# ATC1.net
KiCad netlist of a schematic drawn in EAGLE
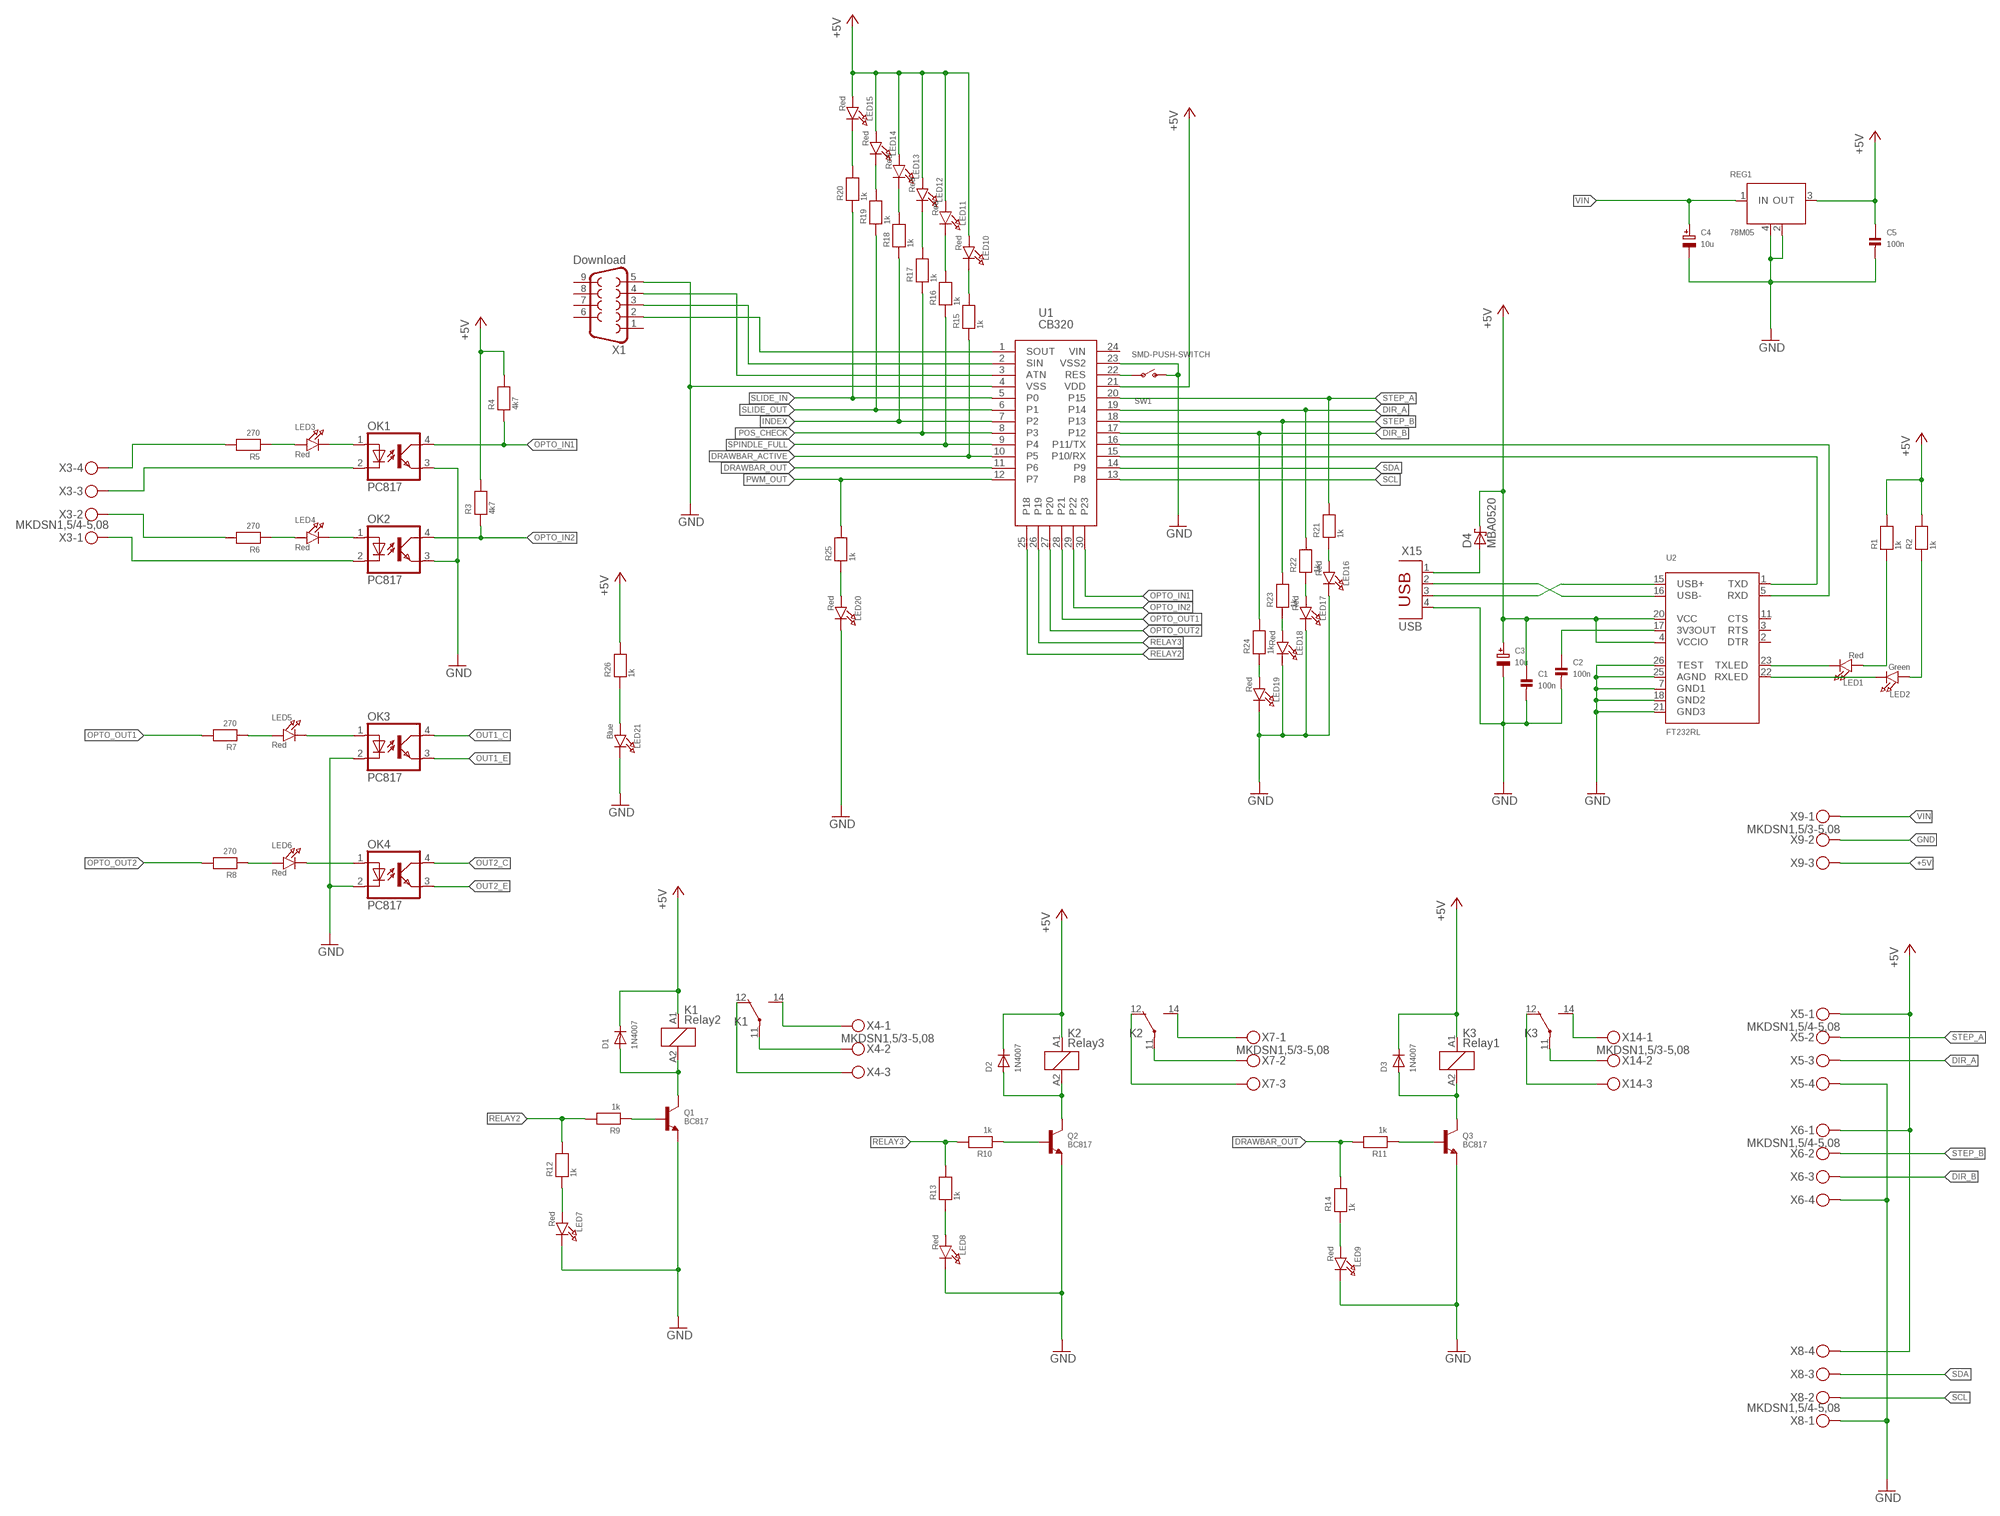
[diagram p0: schematic, sheet 1, part 1 of 2]
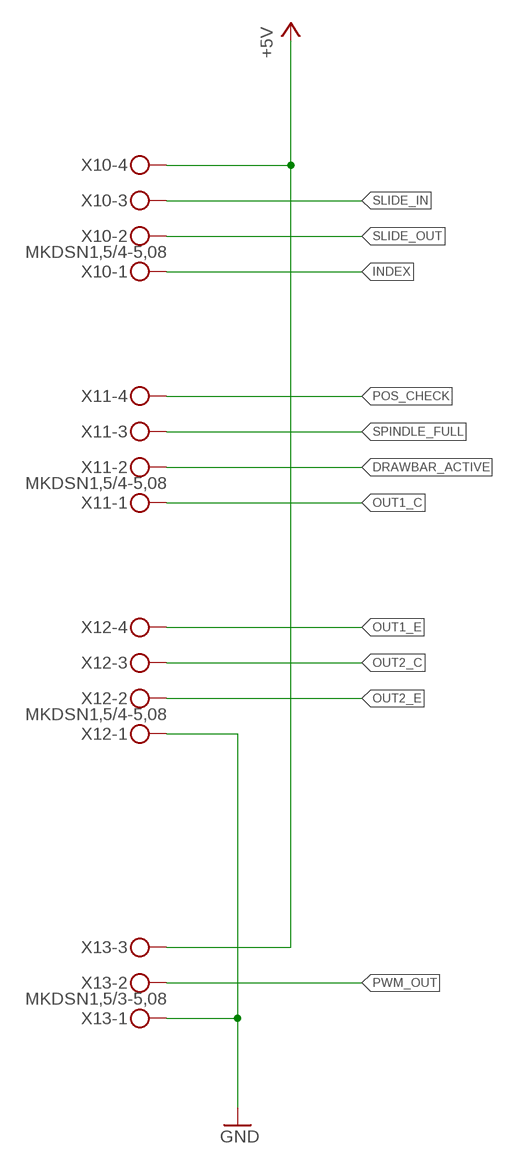
[diagram p1: schematic, sheet 1, part 2 of 2]

(export (version "E")
  (design (tool "Eeschema 10.0.6"))
  (components
    (comp (ref "C1")
      (value "100n")
      (footprint "eagle-import:0805")
      (libsource (lib "eagle-import") (part "CAP_CERAMIC0805"))
    )
    (comp (ref "C2")
      (value "100n")
      (footprint "eagle-import:0805")
      (libsource (lib "eagle-import") (part "CAP_CERAMIC0805"))
    )
    (comp (ref "C3")
      (value "10u")
      (footprint "eagle-import:EIA3216-18_A-R")
      (libsource (lib "eagle-import") (part "CAP_TANTALUMA/3216_REFLOW"))
    )
    (comp (ref "C4")
      (value "10u")
      (footprint "eagle-import:EIA3216-18_A-R")
      (libsource (lib "eagle-import") (part "CAP_TANTALUMA/3216_REFLOW"))
    )
    (comp (ref "C5")
      (value "100n")
      (footprint "eagle-import:0805")
      (libsource (lib "eagle-import") (part "CAP_CERAMIC0805"))
    )
    (comp (ref "D1")
      (value "1N4007")
      (footprint "eagle-import:SOD-123")
      (libsource (lib "eagle-import") (part "DIODESOD-123"))
    )
    (comp (ref "D2")
      (value "1N4007")
      (footprint "eagle-import:SOD-123")
      (libsource (lib "eagle-import") (part "DIODESOD-123"))
    )
    (comp (ref "D3")
      (value "1N4007")
      (footprint "eagle-import:SOD-123")
      (libsource (lib "eagle-import") (part "DIODESOD-123"))
    )
    (comp (ref "D4")
      (value "MBA0520")
      (footprint "eagle-import:SOD123")
      (libsource (lib "eagle-import") (part "MBR0520"))
    )
    (comp (ref "K1")
      (value "Relay2")
      (footprint "eagle-import:SRD")
      (libsource (lib "eagle-import") (part "SRD-05VDC-SL-C"))
    )
    (comp (ref "K2")
      (value "Relay3")
      (footprint "eagle-import:SRD")
      (libsource (lib "eagle-import") (part "SRD-05VDC-SL-C"))
    )
    (comp (ref "K3")
      (value "Relay1")
      (footprint "eagle-import:SRD")
      (libsource (lib "eagle-import") (part "SRD-05VDC-SL-C"))
    )
    (comp (ref "LED1")
      (value "Red")
      (footprint "eagle-import:CHIPLED_0805")
      (libsource (lib "eagle-import") (part "LED0805"))
    )
    (comp (ref "LED2")
      (value "Green")
      (footprint "eagle-import:CHIPLED_0805")
      (libsource (lib "eagle-import") (part "LED0805"))
    )
    (comp (ref "LED3")
      (value "Red")
      (footprint "eagle-import:CHIPLED_0805")
      (libsource (lib "eagle-import") (part "LED0805"))
    )
    (comp (ref "LED4")
      (value "Red")
      (footprint "eagle-import:CHIPLED_0805")
      (libsource (lib "eagle-import") (part "LED0805"))
    )
    (comp (ref "LED5")
      (value "Red")
      (footprint "eagle-import:CHIPLED_0805")
      (libsource (lib "eagle-import") (part "LED0805"))
    )
    (comp (ref "LED6")
      (value "Red")
      (footprint "eagle-import:CHIPLED_0805")
      (libsource (lib "eagle-import") (part "LED0805"))
    )
    (comp (ref "LED7")
      (value "Red")
      (footprint "eagle-import:CHIPLED_0805")
      (libsource (lib "eagle-import") (part "LED0805"))
    )
    (comp (ref "LED8")
      (value "Red")
      (footprint "eagle-import:CHIPLED_0805")
      (libsource (lib "eagle-import") (part "LED0805"))
    )
    (comp (ref "LED9")
      (value "Red")
      (footprint "eagle-import:CHIPLED_0805")
      (libsource (lib "eagle-import") (part "LED0805"))
    )
    (comp (ref "LED10")
      (value "Red")
      (footprint "eagle-import:CHIPLED_0805")
      (libsource (lib "eagle-import") (part "LED0805"))
    )
    (comp (ref "LED11")
      (value "Red")
      (footprint "eagle-import:CHIPLED_0805")
      (libsource (lib "eagle-import") (part "LED0805"))
    )
    (comp (ref "LED12")
      (value "Red")
      (footprint "eagle-import:CHIPLED_0805")
      (libsource (lib "eagle-import") (part "LED0805"))
    )
    (comp (ref "LED13")
      (value "Red")
      (footprint "eagle-import:CHIPLED_0805")
      (libsource (lib "eagle-import") (part "LED0805"))
    )
    (comp (ref "LED14")
      (value "Red")
      (footprint "eagle-import:CHIPLED_0805")
      (libsource (lib "eagle-import") (part "LED0805"))
    )
    (comp (ref "LED15")
      (value "Red")
      (footprint "eagle-import:CHIPLED_0805")
      (libsource (lib "eagle-import") (part "LED0805"))
    )
    (comp (ref "LED16")
      (value "Red")
      (footprint "eagle-import:CHIPLED_0805")
      (libsource (lib "eagle-import") (part "LED0805"))
    )
    (comp (ref "LED17")
      (value "Red")
      (footprint "eagle-import:CHIPLED_0805")
      (libsource (lib "eagle-import") (part "LED0805"))
    )
    (comp (ref "LED18")
      (value "Red")
      (footprint "eagle-import:CHIPLED_0805")
      (libsource (lib "eagle-import") (part "LED0805"))
    )
    (comp (ref "LED19")
      (value "Red")
      (footprint "eagle-import:CHIPLED_0805")
      (libsource (lib "eagle-import") (part "LED0805"))
    )
    (comp (ref "LED20")
      (value "Red")
      (footprint "eagle-import:CHIPLED_0805")
      (libsource (lib "eagle-import") (part "LED0805"))
    )
    (comp (ref "LED21")
      (value "Blue")
      (footprint "eagle-import:CHIPLED_0805")
      (libsource (lib "eagle-import") (part "LED0805"))
    )
    (comp (ref "OK1")
      (value "PC817")
      (footprint "eagle-import:SM4-GW")
      (libsource (lib "eagle-import") (part "PC817"))
    )
    (comp (ref "OK2")
      (value "PC817")
      (footprint "eagle-import:SM4-GW")
      (libsource (lib "eagle-import") (part "PC817"))
    )
    (comp (ref "OK3")
      (value "PC817")
      (footprint "eagle-import:SM4-GW")
      (libsource (lib "eagle-import") (part "PC817"))
    )
    (comp (ref "OK4")
      (value "PC817")
      (footprint "eagle-import:SM4-GW")
      (libsource (lib "eagle-import") (part "PC817"))
    )
    (comp (ref "Q1")
      (value "BC817")
      (footprint "eagle-import:SOT23-WIDE")
      (libsource (lib "eagle-import") (part "TRANSISTOR_NPNWIDE"))
    )
    (comp (ref "Q2")
      (value "BC817")
      (footprint "eagle-import:SOT23-WIDE")
      (libsource (lib "eagle-import") (part "TRANSISTOR_NPNWIDE"))
    )
    (comp (ref "Q3")
      (value "BC817")
      (footprint "eagle-import:SOT23-WIDE")
      (libsource (lib "eagle-import") (part "TRANSISTOR_NPNWIDE"))
    )
    (comp (ref "R1")
      (value "1k")
      (footprint "eagle-import:0805")
      (libsource (lib "eagle-import") (part "RESISTOR0805"))
    )
    (comp (ref "R2")
      (value "1k")
      (footprint "eagle-import:0805")
      (libsource (lib "eagle-import") (part "RESISTOR0805"))
    )
    (comp (ref "R3")
      (value "4k7")
      (footprint "eagle-import:0805")
      (libsource (lib "eagle-import") (part "RESISTOR0805"))
    )
    (comp (ref "R4")
      (value "4k7")
      (footprint "eagle-import:0805")
      (libsource (lib "eagle-import") (part "RESISTOR0805"))
    )
    (comp (ref "R5")
      (value "270")
      (footprint "eagle-import:0805")
      (libsource (lib "eagle-import") (part "RESISTOR0805"))
    )
    (comp (ref "R6")
      (value "270")
      (footprint "eagle-import:0805")
      (libsource (lib "eagle-import") (part "RESISTOR0805"))
    )
    (comp (ref "R7")
      (value "270")
      (footprint "eagle-import:0805")
      (libsource (lib "eagle-import") (part "RESISTOR0805"))
    )
    (comp (ref "R8")
      (value "270")
      (footprint "eagle-import:0805")
      (libsource (lib "eagle-import") (part "RESISTOR0805"))
    )
    (comp (ref "R9")
      (value "1k")
      (footprint "eagle-import:0805")
      (libsource (lib "eagle-import") (part "RESISTOR0805"))
    )
    (comp (ref "R10")
      (value "1k")
      (footprint "eagle-import:0805")
      (libsource (lib "eagle-import") (part "RESISTOR0805"))
    )
    (comp (ref "R11")
      (value "1k")
      (footprint "eagle-import:0805")
      (libsource (lib "eagle-import") (part "RESISTOR0805"))
    )
    (comp (ref "R12")
      (value "1k")
      (footprint "eagle-import:0805")
      (libsource (lib "eagle-import") (part "RESISTOR0805"))
    )
    (comp (ref "R13")
      (value "1k")
      (footprint "eagle-import:0805")
      (libsource (lib "eagle-import") (part "RESISTOR0805"))
    )
    (comp (ref "R14")
      (value "1k")
      (footprint "eagle-import:0805")
      (libsource (lib "eagle-import") (part "RESISTOR0805"))
    )
    (comp (ref "R15")
      (value "1k")
      (footprint "eagle-import:0805")
      (libsource (lib "eagle-import") (part "RESISTOR0805"))
    )
    (comp (ref "R16")
      (value "1k")
      (footprint "eagle-import:0805")
      (libsource (lib "eagle-import") (part "RESISTOR0805"))
    )
    (comp (ref "R17")
      (value "1k")
      (footprint "eagle-import:0805")
      (libsource (lib "eagle-import") (part "RESISTOR0805"))
    )
    (comp (ref "R18")
      (value "1k")
      (footprint "eagle-import:0805")
      (libsource (lib "eagle-import") (part "RESISTOR0805"))
    )
    (comp (ref "R19")
      (value "1k")
      (footprint "eagle-import:0805")
      (libsource (lib "eagle-import") (part "RESISTOR0805"))
    )
    (comp (ref "R20")
      (value "1k")
      (footprint "eagle-import:0805")
      (libsource (lib "eagle-import") (part "RESISTOR0805"))
    )
    (comp (ref "R21")
      (value "1k")
      (footprint "eagle-import:0805")
      (libsource (lib "eagle-import") (part "RESISTOR0805"))
    )
    (comp (ref "R22")
      (value "1k")
      (footprint "eagle-import:0805")
      (libsource (lib "eagle-import") (part "RESISTOR0805"))
    )
    (comp (ref "R23")
      (value "1k")
      (footprint "eagle-import:0805")
      (libsource (lib "eagle-import") (part "RESISTOR0805"))
    )
    (comp (ref "R24")
      (value "1k")
      (footprint "eagle-import:0805")
      (libsource (lib "eagle-import") (part "RESISTOR0805"))
    )
    (comp (ref "R25")
      (value "1k")
      (footprint "eagle-import:0805")
      (libsource (lib "eagle-import") (part "RESISTOR0805"))
    )
    (comp (ref "R26")
      (value "1k")
      (footprint "eagle-import:0805")
      (libsource (lib "eagle-import") (part "RESISTOR0805"))
    )
    (comp (ref "REG1")
      (value "78M05")
      (footprint "eagle-import:UA78M05")
      (libsource (lib "eagle-import") (part "UA78M05"))
    )
    (comp (ref "SW1")
      (value "SMD-PUSH-SWITCH")
      (footprint "eagle-import:PUSH-BUTTON-SMD")
      (libsource (lib "eagle-import") (part "SMD-PUSH-SWITCH"))
    )
    (comp (ref "U1")
      (value "CB320")
      (footprint "eagle-import:DIL24")
      (libsource (lib "eagle-import") (part "CUBLOC-CB320"))
    )
    (comp (ref "U2")
      (value "FT232RL")
      (footprint "eagle-import:SSOP28DB")
      (libsource (lib "eagle-import") (part "FT232RLSSOP28"))
    )
    (comp (ref "X1")
      (value "Download")
      (footprint "eagle-import:F09HP")
      (libsource (lib "eagle-import") (part "F09HP"))
    )
    (comp (ref "X3")
      (value "MKDSN1,5/4-5,08")
      (footprint "eagle-import:MKDSN1,5_4-5,08")
      (libsource (lib "eagle-import") (part "MKDSN1,5/4-5,08"))
    )
    (comp (ref "X4")
      (value "MKDSN1,5/3-5,08")
      (footprint "eagle-import:MKDSN1,5_3-5,08")
      (libsource (lib "eagle-import") (part "MKDSN1,5/3-5,08"))
    )
    (comp (ref "X5")
      (value "MKDSN1,5/4-5,08")
      (footprint "eagle-import:MKDSN1,5_4-5,08")
      (libsource (lib "eagle-import") (part "MKDSN1,5/4-5,08"))
    )
    (comp (ref "X6")
      (value "MKDSN1,5/4-5,08")
      (footprint "eagle-import:MKDSN1,5_4-5,08")
      (libsource (lib "eagle-import") (part "MKDSN1,5/4-5,08"))
    )
    (comp (ref "X7")
      (value "MKDSN1,5/3-5,08")
      (footprint "eagle-import:MKDSN1,5_3-5,08")
      (libsource (lib "eagle-import") (part "MKDSN1,5/3-5,08"))
    )
    (comp (ref "X8")
      (value "MKDSN1,5/4-5,08")
      (footprint "eagle-import:MKDSN1,5_4-5,08")
      (libsource (lib "eagle-import") (part "MKDSN1,5/4-5,08"))
    )
    (comp (ref "X9")
      (value "MKDSN1,5/3-5,08")
      (footprint "eagle-import:MKDSN1,5_3-5,08")
      (libsource (lib "eagle-import") (part "MKDSN1,5/3-5,08"))
    )
    (comp (ref "X10")
      (value "MKDSN1,5/4-5,08")
      (footprint "eagle-import:MKDSN1,5_4-5,08")
      (libsource (lib "eagle-import") (part "MKDSN1,5/4-5,08"))
    )
    (comp (ref "X11")
      (value "MKDSN1,5/4-5,08")
      (footprint "eagle-import:MKDSN1,5_4-5,08")
      (libsource (lib "eagle-import") (part "MKDSN1,5/4-5,08"))
    )
    (comp (ref "X12")
      (value "MKDSN1,5/4-5,08")
      (footprint "eagle-import:MKDSN1,5_4-5,08")
      (libsource (lib "eagle-import") (part "MKDSN1,5/4-5,08"))
    )
    (comp (ref "X13")
      (value "MKDSN1,5/3-5,08")
      (footprint "eagle-import:MKDSN1,5_3-5,08")
      (libsource (lib "eagle-import") (part "MKDSN1,5/3-5,08"))
    )
    (comp (ref "X14")
      (value "MKDSN1,5/3-5,08")
      (footprint "eagle-import:MKDSN1,5_3-5,08")
      (libsource (lib "eagle-import") (part "MKDSN1,5/3-5,08"))
    )
    (comp (ref "X15")
      (value "USB")
      (footprint "eagle-import:PN61729")
      (libsource (lib "eagle-import") (part "PN61729"))
    )
  )
  (nets
    (net (code "1") (name "+5V") (class "Default")
      (node (ref "C1") (pin "1") (pinfunction "P$1_1") (pintype "passive"))
      (node (ref "C3") (pin "+") (pinfunction "+_+") (pintype "passive"))
      (node (ref "C5") (pin "1") (pinfunction "P$1_1") (pintype "passive"))
      (node (ref "D1") (pin "C") (pinfunction "C_C") (pintype "passive"))
      (node (ref "D2") (pin "C") (pinfunction "C_C") (pintype "passive"))
      (node (ref "D3") (pin "C") (pinfunction "C_C") (pintype "passive"))
      (node (ref "D4") (pin "C") (pinfunction "C_C") (pintype "passive"))
      (node (ref "K1") (pin "A1") (pinfunction "1_A1") (pintype "passive"))
      (node (ref "K2") (pin "A1") (pinfunction "1_A1") (pintype "passive"))
      (node (ref "K3") (pin "A1") (pinfunction "1_A1") (pintype "passive"))
      (node (ref "LED10") (pin "A") (pinfunction "A_A") (pintype "passive"))
      (node (ref "LED11") (pin "A") (pinfunction "A_A") (pintype "passive"))
      (node (ref "LED12") (pin "A") (pinfunction "A_A") (pintype "passive"))
      (node (ref "LED13") (pin "A") (pinfunction "A_A") (pintype "passive"))
      (node (ref "LED14") (pin "A") (pinfunction "A_A") (pintype "passive"))
      (node (ref "LED15") (pin "A") (pinfunction "A_A") (pintype "passive"))
      (node (ref "R1") (pin "2") (pinfunction "2_2") (pintype "passive"))
      (node (ref "R2") (pin "2") (pinfunction "2_2") (pintype "passive"))
      (node (ref "R26") (pin "2") (pinfunction "2_2") (pintype "passive"))
      (node (ref "R3") (pin "2") (pinfunction "2_2") (pintype "passive"))
      (node (ref "R4") (pin "2") (pinfunction "2_2") (pintype "passive"))
      (node (ref "REG1") (pin "3") (pinfunction "OUT_3") (pintype "passive"))
      (node (ref "U1") (pin "21") (pinfunction "VDD_21") (pintype "power_in"))
      (node (ref "U2") (pin "20") (pinfunction "VCC_20") (pintype "power_in"))
      (node (ref "U2") (pin "4") (pinfunction "VCCIO_4") (pintype "power_in"))
      (node (ref "X10") (pin "4") (pinfunction "KL_4") (pintype "passive"))
      (node (ref "X13") (pin "3") (pinfunction "KL_3") (pintype "passive"))
      (node (ref "X5") (pin "1") (pinfunction "KL_1") (pintype "passive"))
      (node (ref "X6") (pin "1") (pinfunction "KL_1") (pintype "passive"))
      (node (ref "X8") (pin "4") (pinfunction "KL_4") (pintype "passive"))
      (node (ref "X9") (pin "3") (pinfunction "KL_3") (pintype "passive"))
    )
    (net (code "2") (name "DIR_A") (class "Default")
      (node (ref "R22") (pin "2") (pinfunction "2_2") (pintype "passive"))
      (node (ref "U1") (pin "19") (pinfunction "P14_19") (pintype "bidirectional"))
      (node (ref "X5") (pin "3") (pinfunction "KL_3") (pintype "passive"))
    )
    (net (code "3") (name "DIR_B") (class "Default")
      (node (ref "R24") (pin "2") (pinfunction "2_2") (pintype "passive"))
      (node (ref "U1") (pin "17") (pinfunction "P12_17") (pintype "bidirectional"))
      (node (ref "X6") (pin "3") (pinfunction "KL_3") (pintype "passive"))
    )
    (net (code "4") (name "DRAWBAR_ACTIVE") (class "Default")
      (node (ref "R15") (pin "1") (pinfunction "1_1") (pintype "passive"))
      (node (ref "U1") (pin "10") (pinfunction "P5_10") (pintype "bidirectional"))
      (node (ref "X11") (pin "2") (pinfunction "KL_2") (pintype "passive"))
    )
    (net (code "5") (name "DRAWBAR_OUT") (class "Default")
      (node (ref "R11") (pin "2") (pinfunction "2_2") (pintype "passive"))
      (node (ref "R14") (pin "2") (pinfunction "2_2") (pintype "passive"))
      (node (ref "U1") (pin "11") (pinfunction "P6_11") (pintype "bidirectional"))
    )
    (net (code "6") (name "GND") (class "Default")
      (node (ref "C1") (pin "2") (pinfunction "P$2_2") (pintype "passive"))
      (node (ref "C2") (pin "2") (pinfunction "P$2_2") (pintype "passive"))
      (node (ref "C3") (pin "-") (pinfunction "-_-") (pintype "passive"))
      (node (ref "C4") (pin "-") (pinfunction "-_-") (pintype "passive"))
      (node (ref "C5") (pin "2") (pinfunction "P$2_2") (pintype "passive"))
      (node (ref "LED16") (pin "C") (pinfunction "C_C") (pintype "passive"))
      (node (ref "LED17") (pin "C") (pinfunction "C_C") (pintype "passive"))
      (node (ref "LED18") (pin "C") (pinfunction "C_C") (pintype "passive"))
      (node (ref "LED19") (pin "C") (pinfunction "C_C") (pintype "passive"))
      (node (ref "LED20") (pin "C") (pinfunction "C_C") (pintype "passive"))
      (node (ref "LED21") (pin "C") (pinfunction "C_C") (pintype "passive"))
      (node (ref "LED7") (pin "C") (pinfunction "C_C") (pintype "passive"))
      (node (ref "LED8") (pin "C") (pinfunction "C_C") (pintype "passive"))
      (node (ref "LED9") (pin "C") (pinfunction "C_C") (pintype "passive"))
      (node (ref "OK1") (pin "3") (pinfunction "EMIT_3") (pintype "passive"))
      (node (ref "OK2") (pin "3") (pinfunction "EMIT_3") (pintype "passive"))
      (node (ref "OK3") (pin "2") (pinfunction "C_2") (pintype "passive"))
      (node (ref "OK4") (pin "2") (pinfunction "C_2") (pintype "passive"))
      (node (ref "Q1") (pin "2") (pinfunction "E_2") (pintype "passive"))
      (node (ref "Q2") (pin "2") (pinfunction "E_2") (pintype "passive"))
      (node (ref "Q3") (pin "2") (pinfunction "E_2") (pintype "passive"))
      (node (ref "REG1") (pin "2") (pinfunction "COMMON1_2") (pintype "passive"))
      (node (ref "REG1") (pin "4") (pinfunction "COMMON2_4") (pintype "passive"))
      (node (ref "SW1") (pin "P$2") (pinfunction "S_P$2") (pintype "passive"))
      (node (ref "U1") (pin "23") (pinfunction "VSS2_23") (pintype "power_in"))
      (node (ref "U1") (pin "4") (pinfunction "VSS_4") (pintype "power_in"))
      (node (ref "U2") (pin "18") (pinfunction "GND2_18") (pintype "power_in"))
      (node (ref "U2") (pin "21") (pinfunction "GND3_21") (pintype "power_in"))
      (node (ref "U2") (pin "25") (pinfunction "AGND_25") (pintype "power_in"))
      (node (ref "U2") (pin "26") (pinfunction "TEST_26") (pintype "input"))
      (node (ref "U2") (pin "7") (pinfunction "GND1_7") (pintype "power_in"))
      (node (ref "X1") (pin "5") (pinfunction "5_5") (pintype "passive"))
      (node (ref "X12") (pin "1") (pinfunction "KL_1") (pintype "passive"))
      (node (ref "X13") (pin "1") (pinfunction "KL_1") (pintype "passive"))
      (node (ref "X15") (pin "4") (pinfunction "4_4") (pintype "passive"))
      (node (ref "X5") (pin "4") (pinfunction "KL_4") (pintype "passive"))
      (node (ref "X6") (pin "4") (pinfunction "KL_4") (pintype "passive"))
      (node (ref "X8") (pin "1") (pinfunction "KL_1") (pintype "passive"))
      (node (ref "X9") (pin "2") (pinfunction "KL_2") (pintype "passive"))
    )
    (net (code "7") (name "INDEX") (class "Default")
      (node (ref "R18") (pin "1") (pinfunction "1_1") (pintype "passive"))
      (node (ref "U1") (pin "7") (pinfunction "P2_7") (pintype "bidirectional"))
      (node (ref "X10") (pin "1") (pinfunction "KL_1") (pintype "passive"))
    )
    (net (code "8") (name "Net-(C2-P$1)") (class "Default")
      (node (ref "C2") (pin "1") (pinfunction "P$1_1") (pintype "passive"))
      (node (ref "U2") (pin "17") (pinfunction "3V3OUT_17") (pintype "power_in"))
    )
    (net (code "9") (name "Net-(D4-PadA)") (class "Default")
      (node (ref "D4") (pin "A") (pinfunction "A_A") (pintype "passive"))
      (node (ref "X15") (pin "1") (pinfunction "1_1") (pintype "passive"))
    )
    (net (code "10") (name "Net-(K1A-C)") (class "Default")
      (node (ref "K1") (pin "12") (pinfunction "C_12") (pintype "passive"))
      (node (ref "X4") (pin "3") (pinfunction "KL_3") (pintype "passive"))
    )
    (net (code "11") (name "Net-(K1A-O)") (class "Default")
      (node (ref "K1") (pin "14") (pinfunction "O_14") (pintype "passive"))
      (node (ref "X4") (pin "1") (pinfunction "KL_1") (pintype "passive"))
    )
    (net (code "12") (name "Net-(K1A-P)") (class "Default")
      (node (ref "K1") (pin "11") (pinfunction "P_11") (pintype "passive"))
      (node (ref "X4") (pin "2") (pinfunction "KL_2") (pintype "passive"))
    )
    (net (code "13") (name "Net-(K1B-2)") (class "Default")
      (node (ref "D1") (pin "A") (pinfunction "A_A") (pintype "passive"))
      (node (ref "K1") (pin "A2") (pinfunction "2_A2") (pintype "passive"))
      (node (ref "Q1") (pin "3") (pinfunction "C_3") (pintype "passive"))
    )
    (net (code "14") (name "Net-(K2A-C)") (class "Default")
      (node (ref "K2") (pin "12") (pinfunction "C_12") (pintype "passive"))
      (node (ref "X7") (pin "3") (pinfunction "KL_3") (pintype "passive"))
    )
    (net (code "15") (name "Net-(K2A-O)") (class "Default")
      (node (ref "K2") (pin "14") (pinfunction "O_14") (pintype "passive"))
      (node (ref "X7") (pin "1") (pinfunction "KL_1") (pintype "passive"))
    )
    (net (code "16") (name "Net-(K2A-P)") (class "Default")
      (node (ref "K2") (pin "11") (pinfunction "P_11") (pintype "passive"))
      (node (ref "X7") (pin "2") (pinfunction "KL_2") (pintype "passive"))
    )
    (net (code "17") (name "Net-(K2B-2)") (class "Default")
      (node (ref "D2") (pin "A") (pinfunction "A_A") (pintype "passive"))
      (node (ref "K2") (pin "A2") (pinfunction "2_A2") (pintype "passive"))
      (node (ref "Q2") (pin "3") (pinfunction "C_3") (pintype "passive"))
    )
    (net (code "18") (name "Net-(K3A-C)") (class "Default")
      (node (ref "K3") (pin "12") (pinfunction "C_12") (pintype "passive"))
      (node (ref "X14") (pin "3") (pinfunction "KL_3") (pintype "passive"))
    )
    (net (code "19") (name "Net-(K3A-O)") (class "Default")
      (node (ref "K3") (pin "14") (pinfunction "O_14") (pintype "passive"))
      (node (ref "X14") (pin "1") (pinfunction "KL_1") (pintype "passive"))
    )
    (net (code "20") (name "Net-(K3A-P)") (class "Default")
      (node (ref "K3") (pin "11") (pinfunction "P_11") (pintype "passive"))
      (node (ref "X14") (pin "2") (pinfunction "KL_2") (pintype "passive"))
    )
    (net (code "21") (name "Net-(K3B-2)") (class "Default")
      (node (ref "D3") (pin "A") (pinfunction "A_A") (pintype "passive"))
      (node (ref "K3") (pin "A2") (pinfunction "2_A2") (pintype "passive"))
      (node (ref "Q3") (pin "3") (pinfunction "C_3") (pintype "passive"))
    )
    (net (code "22") (name "Net-(LED1-PadA)") (class "Default")
      (node (ref "LED1") (pin "A") (pinfunction "A_A") (pintype "passive"))
      (node (ref "R1") (pin "1") (pinfunction "1_1") (pintype "passive"))
    )
    (net (code "23") (name "Net-(LED2-PadA)") (class "Default")
      (node (ref "LED2") (pin "A") (pinfunction "A_A") (pintype "passive"))
      (node (ref "R2") (pin "1") (pinfunction "1_1") (pintype "passive"))
    )
    (net (code "24") (name "Net-(LED3-PadA)") (class "Default")
      (node (ref "LED3") (pin "A") (pinfunction "A_A") (pintype "passive"))
      (node (ref "R5") (pin "1") (pinfunction "1_1") (pintype "passive"))
    )
    (net (code "25") (name "Net-(LED4-PadA)") (class "Default")
      (node (ref "LED4") (pin "A") (pinfunction "A_A") (pintype "passive"))
      (node (ref "R6") (pin "1") (pinfunction "1_1") (pintype "passive"))
    )
    (net (code "26") (name "Net-(LED5-PadA)") (class "Default")
      (node (ref "LED5") (pin "A") (pinfunction "A_A") (pintype "passive"))
      (node (ref "R7") (pin "1") (pinfunction "1_1") (pintype "passive"))
    )
    (net (code "27") (name "Net-(LED6-PadA)") (class "Default")
      (node (ref "LED6") (pin "A") (pinfunction "A_A") (pintype "passive"))
      (node (ref "R8") (pin "1") (pinfunction "1_1") (pintype "passive"))
    )
    (net (code "28") (name "Net-(LED7-PadA)") (class "Default")
      (node (ref "LED7") (pin "A") (pinfunction "A_A") (pintype "passive"))
      (node (ref "R12") (pin "1") (pinfunction "1_1") (pintype "passive"))
    )
    (net (code "29") (name "Net-(LED8-PadA)") (class "Default")
      (node (ref "LED8") (pin "A") (pinfunction "A_A") (pintype "passive"))
      (node (ref "R13") (pin "1") (pinfunction "1_1") (pintype "passive"))
    )
    (net (code "30") (name "Net-(LED9-PadA)") (class "Default")
      (node (ref "LED9") (pin "A") (pinfunction "A_A") (pintype "passive"))
      (node (ref "R14") (pin "1") (pinfunction "1_1") (pintype "passive"))
    )
    (net (code "31") (name "Net-(LED10-PadC)") (class "Default")
      (node (ref "LED10") (pin "C") (pinfunction "C_C") (pintype "passive"))
      (node (ref "R15") (pin "2") (pinfunction "2_2") (pintype "passive"))
    )
    (net (code "32") (name "Net-(LED11-PadC)") (class "Default")
      (node (ref "LED11") (pin "C") (pinfunction "C_C") (pintype "passive"))
      (node (ref "R16") (pin "2") (pinfunction "2_2") (pintype "passive"))
    )
    (net (code "33") (name "Net-(LED12-PadC)") (class "Default")
      (node (ref "LED12") (pin "C") (pinfunction "C_C") (pintype "passive"))
      (node (ref "R17") (pin "2") (pinfunction "2_2") (pintype "passive"))
    )
    (net (code "34") (name "Net-(LED13-PadC)") (class "Default")
      (node (ref "LED13") (pin "C") (pinfunction "C_C") (pintype "passive"))
      (node (ref "R18") (pin "2") (pinfunction "2_2") (pintype "passive"))
    )
    (net (code "35") (name "Net-(LED14-PadC)") (class "Default")
      (node (ref "LED14") (pin "C") (pinfunction "C_C") (pintype "passive"))
      (node (ref "R19") (pin "2") (pinfunction "2_2") (pintype "passive"))
    )
    (net (code "36") (name "Net-(LED15-PadC)") (class "Default")
      (node (ref "LED15") (pin "C") (pinfunction "C_C") (pintype "passive"))
      (node (ref "R20") (pin "2") (pinfunction "2_2") (pintype "passive"))
    )
    (net (code "37") (name "Net-(LED16-PadA)") (class "Default")
      (node (ref "LED16") (pin "A") (pinfunction "A_A") (pintype "passive"))
      (node (ref "R21") (pin "1") (pinfunction "1_1") (pintype "passive"))
    )
    (net (code "38") (name "Net-(LED17-PadA)") (class "Default")
      (node (ref "LED17") (pin "A") (pinfunction "A_A") (pintype "passive"))
      (node (ref "R22") (pin "1") (pinfunction "1_1") (pintype "passive"))
    )
    (net (code "39") (name "Net-(LED18-PadA)") (class "Default")
      (node (ref "LED18") (pin "A") (pinfunction "A_A") (pintype "passive"))
      (node (ref "R23") (pin "1") (pinfunction "1_1") (pintype "passive"))
    )
    (net (code "40") (name "Net-(LED19-PadA)") (class "Default")
      (node (ref "LED19") (pin "A") (pinfunction "A_A") (pintype "passive"))
      (node (ref "R24") (pin "1") (pinfunction "1_1") (pintype "passive"))
    )
    (net (code "41") (name "Net-(LED20-PadA)") (class "Default")
      (node (ref "LED20") (pin "A") (pinfunction "A_A") (pintype "passive"))
      (node (ref "R25") (pin "1") (pinfunction "1_1") (pintype "passive"))
    )
    (net (code "42") (name "Net-(LED21-PadA)") (class "Default")
      (node (ref "LED21") (pin "A") (pinfunction "A_A") (pintype "passive"))
      (node (ref "R26") (pin "1") (pinfunction "1_1") (pintype "passive"))
    )
    (net (code "43") (name "Net-(OK1-A)") (class "Default")
      (node (ref "LED3") (pin "C") (pinfunction "C_C") (pintype "passive"))
      (node (ref "OK1") (pin "1") (pinfunction "A_1") (pintype "passive"))
    )
    (net (code "44") (name "Net-(OK1-C)") (class "Default")
      (node (ref "OK1") (pin "2") (pinfunction "C_2") (pintype "passive"))
      (node (ref "X3") (pin "3") (pinfunction "KL_3") (pintype "passive"))
    )
    (net (code "45") (name "Net-(OK2-A)") (class "Default")
      (node (ref "LED4") (pin "C") (pinfunction "C_C") (pintype "passive"))
      (node (ref "OK2") (pin "1") (pinfunction "A_1") (pintype "passive"))
    )
    (net (code "46") (name "Net-(OK2-C)") (class "Default")
      (node (ref "OK2") (pin "2") (pinfunction "C_2") (pintype "passive"))
      (node (ref "X3") (pin "1") (pinfunction "KL_1") (pintype "passive"))
    )
    (net (code "47") (name "Net-(OK3-A)") (class "Default")
      (node (ref "LED5") (pin "C") (pinfunction "C_C") (pintype "passive"))
      (node (ref "OK3") (pin "1") (pinfunction "A_1") (pintype "passive"))
    )
    (net (code "48") (name "Net-(OK4-A)") (class "Default")
      (node (ref "LED6") (pin "C") (pinfunction "C_C") (pintype "passive"))
      (node (ref "OK4") (pin "1") (pinfunction "A_1") (pintype "passive"))
    )
    (net (code "49") (name "Net-(Q1-B)") (class "Default")
      (node (ref "Q1") (pin "1") (pinfunction "B_1") (pintype "passive"))
      (node (ref "R9") (pin "1") (pinfunction "1_1") (pintype "passive"))
    )
    (net (code "50") (name "Net-(Q2-B)") (class "Default")
      (node (ref "Q2") (pin "1") (pinfunction "B_1") (pintype "passive"))
      (node (ref "R10") (pin "1") (pinfunction "1_1") (pintype "passive"))
    )
    (net (code "51") (name "Net-(Q3-B)") (class "Default")
      (node (ref "Q3") (pin "1") (pinfunction "B_1") (pintype "passive"))
      (node (ref "R11") (pin "1") (pinfunction "1_1") (pintype "passive"))
    )
    (net (code "52") (name "Net-(SW1-P)") (class "Default")
      (node (ref "SW1") (pin "P$1") (pinfunction "P_P$1") (pintype "passive"))
      (node (ref "U1") (pin "22") (pinfunction "RES_22") (pintype "input"))
    )
    (net (code "53") (name "Net-(U1-ATN)") (class "Default")
      (node (ref "U1") (pin "3") (pinfunction "ATN_3") (pintype "input"))
      (node (ref "X1") (pin "4") (pinfunction "4_4") (pintype "passive"))
    )
    (net (code "54") (name "Net-(U1-P10{slash}RX)") (class "Default")
      (node (ref "U1") (pin "15") (pinfunction "P10/RX_15") (pintype "bidirectional"))
      (node (ref "U2") (pin "1") (pinfunction "TXD_1") (pintype "output"))
    )
    (net (code "55") (name "Net-(U1-P11{slash}TX)") (class "Default")
      (node (ref "U1") (pin "16") (pinfunction "P11/TX_16") (pintype "bidirectional"))
      (node (ref "U2") (pin "5") (pinfunction "RXD_5") (pintype "input"))
    )
    (net (code "56") (name "Net-(U1-SIN)") (class "Default")
      (node (ref "U1") (pin "2") (pinfunction "SIN_2") (pintype "input"))
      (node (ref "X1") (pin "3") (pinfunction "3_3") (pintype "passive"))
    )
    (net (code "57") (name "Net-(U1-SOUT)") (class "Default")
      (node (ref "U1") (pin "1") (pinfunction "SOUT_1") (pintype "output"))
      (node (ref "X1") (pin "2") (pinfunction "2_2") (pintype "passive"))
    )
    (net (code "58") (name "Net-(U2-RXLED)") (class "Default")
      (node (ref "LED2") (pin "C") (pinfunction "C_C") (pintype "passive"))
      (node (ref "U2") (pin "22") (pinfunction "RXLED_22") (pintype "bidirectional"))
    )
    (net (code "59") (name "Net-(U2-TXLED)") (class "Default")
      (node (ref "LED1") (pin "C") (pinfunction "C_C") (pintype "passive"))
      (node (ref "U2") (pin "23") (pinfunction "TXLED_23") (pintype "bidirectional"))
    )
    (net (code "60") (name "Net-(U2-USB+)") (class "Default")
      (node (ref "U2") (pin "15") (pinfunction "USB+_15") (pintype "bidirectional"))
      (node (ref "X15") (pin "3") (pinfunction "3_3") (pintype "passive"))
    )
    (net (code "61") (name "Net-(U2-USB-)") (class "Default")
      (node (ref "U2") (pin "16") (pinfunction "USB-_16") (pintype "bidirectional"))
      (node (ref "X15") (pin "2") (pinfunction "2_2") (pintype "passive"))
    )
    (net (code "62") (name "Net-(X3B-KL)") (class "Default")
      (node (ref "R6") (pin "2") (pinfunction "2_2") (pintype "passive"))
      (node (ref "X3") (pin "2") (pinfunction "KL_2") (pintype "passive"))
    )
    (net (code "63") (name "Net-(X3D-KL)") (class "Default")
      (node (ref "R5") (pin "2") (pinfunction "2_2") (pintype "passive"))
      (node (ref "X3") (pin "4") (pinfunction "KL_4") (pintype "passive"))
    )
    (net (code "64") (name "OPTO_IN1") (class "Default")
      (node (ref "OK1") (pin "4") (pinfunction "COL_4") (pintype "passive"))
      (node (ref "R4") (pin "1") (pinfunction "1_1") (pintype "passive"))
      (node (ref "U1") (pin "30") (pinfunction "P23_30") (pintype "bidirectional"))
    )
    (net (code "65") (name "OPTO_IN2") (class "Default")
      (node (ref "OK2") (pin "4") (pinfunction "COL_4") (pintype "passive"))
      (node (ref "R3") (pin "1") (pinfunction "1_1") (pintype "passive"))
      (node (ref "U1") (pin "29") (pinfunction "P22_29") (pintype "bidirectional"))
    )
    (net (code "66") (name "OPTO_OUT1") (class "Default")
      (node (ref "R7") (pin "2") (pinfunction "2_2") (pintype "passive"))
      (node (ref "U1") (pin "28") (pinfunction "P21_28") (pintype "bidirectional"))
    )
    (net (code "67") (name "OPTO_OUT2") (class "Default")
      (node (ref "R8") (pin "2") (pinfunction "2_2") (pintype "passive"))
      (node (ref "U1") (pin "27") (pinfunction "P20_27") (pintype "bidirectional"))
    )
    (net (code "68") (name "OUT1_C") (class "Default")
      (node (ref "OK3") (pin "4") (pinfunction "COL_4") (pintype "passive"))
      (node (ref "X11") (pin "1") (pinfunction "KL_1") (pintype "passive"))
    )
    (net (code "69") (name "OUT1_E") (class "Default")
      (node (ref "OK3") (pin "3") (pinfunction "EMIT_3") (pintype "passive"))
      (node (ref "X12") (pin "4") (pinfunction "KL_4") (pintype "passive"))
    )
    (net (code "70") (name "OUT2_C") (class "Default")
      (node (ref "OK4") (pin "4") (pinfunction "COL_4") (pintype "passive"))
      (node (ref "X12") (pin "3") (pinfunction "KL_3") (pintype "passive"))
    )
    (net (code "71") (name "OUT2_E") (class "Default")
      (node (ref "OK4") (pin "3") (pinfunction "EMIT_3") (pintype "passive"))
      (node (ref "X12") (pin "2") (pinfunction "KL_2") (pintype "passive"))
    )
    (net (code "72") (name "POS_CHECK") (class "Default")
      (node (ref "R17") (pin "1") (pinfunction "1_1") (pintype "passive"))
      (node (ref "U1") (pin "8") (pinfunction "P3_8") (pintype "bidirectional"))
      (node (ref "X11") (pin "4") (pinfunction "KL_4") (pintype "passive"))
    )
    (net (code "73") (name "PWM_OUT") (class "Default")
      (node (ref "R25") (pin "2") (pinfunction "2_2") (pintype "passive"))
      (node (ref "U1") (pin "12") (pinfunction "P7_12") (pintype "bidirectional"))
      (node (ref "X13") (pin "2") (pinfunction "KL_2") (pintype "passive"))
    )
    (net (code "74") (name "RELAY2") (class "Default")
      (node (ref "R12") (pin "2") (pinfunction "2_2") (pintype "passive"))
      (node (ref "R9") (pin "2") (pinfunction "2_2") (pintype "passive"))
      (node (ref "U1") (pin "25") (pinfunction "P18_25") (pintype "bidirectional"))
    )
    (net (code "75") (name "RELAY3") (class "Default")
      (node (ref "R10") (pin "2") (pinfunction "2_2") (pintype "passive"))
      (node (ref "R13") (pin "2") (pinfunction "2_2") (pintype "passive"))
      (node (ref "U1") (pin "26") (pinfunction "P19_26") (pintype "bidirectional"))
    )
    (net (code "76") (name "SCL") (class "Default")
      (node (ref "U1") (pin "13") (pinfunction "P8_13") (pintype "bidirectional"))
      (node (ref "X8") (pin "2") (pinfunction "KL_2") (pintype "passive"))
    )
    (net (code "77") (name "SDA") (class "Default")
      (node (ref "U1") (pin "14") (pinfunction "P9_14") (pintype "bidirectional"))
      (node (ref "X8") (pin "3") (pinfunction "KL_3") (pintype "passive"))
    )
    (net (code "78") (name "SLIDE_IN") (class "Default")
      (node (ref "R20") (pin "1") (pinfunction "1_1") (pintype "passive"))
      (node (ref "U1") (pin "5") (pinfunction "P0_5") (pintype "bidirectional"))
      (node (ref "X10") (pin "3") (pinfunction "KL_3") (pintype "passive"))
    )
    (net (code "79") (name "SLIDE_OUT") (class "Default")
      (node (ref "R19") (pin "1") (pinfunction "1_1") (pintype "passive"))
      (node (ref "U1") (pin "6") (pinfunction "P1_6") (pintype "input"))
      (node (ref "X10") (pin "2") (pinfunction "KL_2") (pintype "passive"))
    )
    (net (code "80") (name "SPINDLE_FULL") (class "Default")
      (node (ref "R16") (pin "1") (pinfunction "1_1") (pintype "passive"))
      (node (ref "U1") (pin "9") (pinfunction "P4_9") (pintype "bidirectional"))
      (node (ref "X11") (pin "3") (pinfunction "KL_3") (pintype "passive"))
    )
    (net (code "81") (name "STEP_A") (class "Default")
      (node (ref "R21") (pin "2") (pinfunction "2_2") (pintype "passive"))
      (node (ref "U1") (pin "20") (pinfunction "P15_20") (pintype "bidirectional"))
      (node (ref "X5") (pin "2") (pinfunction "KL_2") (pintype "passive"))
    )
    (net (code "82") (name "STEP_B") (class "Default")
      (node (ref "R23") (pin "2") (pinfunction "2_2") (pintype "passive"))
      (node (ref "U1") (pin "18") (pinfunction "P13_18") (pintype "bidirectional"))
      (node (ref "X6") (pin "2") (pinfunction "KL_2") (pintype "passive"))
    )
    (net (code "83") (name "VIN") (class "Default")
      (node (ref "C4") (pin "+") (pinfunction "+_+") (pintype "passive"))
      (node (ref "REG1") (pin "1") (pinfunction "IN_1") (pintype "input"))
      (node (ref "X9") (pin "1") (pinfunction "KL_1") (pintype "passive"))
    )
    (net (code "84") (name "unconnected-(U1-VIN-Pad24)") (class "Default")
      (node (ref "U1") (pin "24") (pinfunction "VIN_24") (pintype "bidirectional"))
    )
    (net (code "85") (name "unconnected-(U2-CTS-Pad11)") (class "Default")
      (node (ref "U2") (pin "11") (pinfunction "CTS_11") (pintype "bidirectional"))
    )
    (net (code "86") (name "unconnected-(U2-DTR-Pad2)") (class "Default")
      (node (ref "U2") (pin "2") (pinfunction "DTR_2") (pintype "bidirectional"))
    )
    (net (code "87") (name "unconnected-(U2-RTS-Pad3)") (class "Default")
      (node (ref "U2") (pin "3") (pinfunction "RTS_3") (pintype "bidirectional"))
    )
    (net (code "88") (name "unconnected-(X1-Pad1)") (class "Default")
      (node (ref "X1") (pin "1") (pinfunction "1_1") (pintype "passive"))
    )
    (net (code "89") (name "unconnected-(X1-Pad6)") (class "Default")
      (node (ref "X1") (pin "6") (pinfunction "6_6") (pintype "passive"))
    )
    (net (code "90") (name "unconnected-(X1-Pad7)") (class "Default")
      (node (ref "X1") (pin "7") (pinfunction "7_7") (pintype "passive"))
    )
    (net (code "91") (name "unconnected-(X1-Pad8)") (class "Default")
      (node (ref "X1") (pin "8") (pinfunction "8_8") (pintype "passive"))
    )
    (net (code "92") (name "unconnected-(X1-Pad9)") (class "Default")
      (node (ref "X1") (pin "9") (pinfunction "9_9") (pintype "passive"))
    )
  )
)
